# USB.net
KiCad netlist of a schematic drawn in Altium Designer
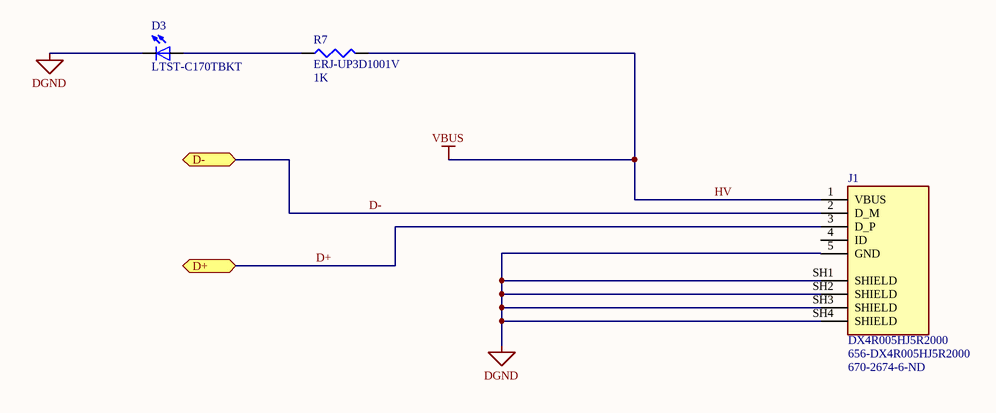
[diagram p0: USB.SchDoc]

(export (version "E")
  (design (tool "Eeschema 10.0.6"))
  (components
    (comp (ref "D3")
      (value "LTST-C170TBKT")
      (footprint "DIOC200X125X110")
      (description "Blue 470nm LED Indication - Discrete 3.3V 0805 _2012 Metric_")
      (fields (field (name "MF") "Lite-On Inc.") (field (name "DIGI-KEY_PART_NUMBER") "160-1579-1-ND"))
      (libsource (lib "Led") (part "LTST-C170TBKT"))
    )
    (comp (ref "J1")
      (value "DX4R005HJ5R2000")
      (footprint "DX4R005HJ5R2000:JAE_DX4R005HJ5R2000")
      (description "USB - micro B USB 2.0 Receptacle Connector 5 Position Surface Mount, Right Angle")
      (fields
        (field (name "MF") "JAE Electronics")
        (field (name "SUPPLIER PART NUMBER 1") "656-DX4R005HJ5R2000")
        (field (name "SUPPLIER PART NUMBER 2") "670-2674-6-ND")
      )
      (libsource (lib "DX4R005HJ5R2000") (part "DX4R005HJ5R2000"))
    )
    (comp (ref "R7")
      (value "ERJ-UP3D1001V")
      (footprint "J1-0603")
      (description "Resistor")
      (fields (field (name "ALTIUM_VALUE") "1K") (field (name "PUBLISHER") "Altium Limited"))
      (libsource (lib "Miscellaneous Devices") (part "Res3"))
    )
  )
  (nets
    (net (code "1") (name "/D+") (class "Default")
      (node (ref "J1") (pin "3") (pinfunction "D_P_3") (pintype "passive"))
    )
    (net (code "2") (name "/D-") (class "Default")
      (node (ref "J1") (pin "2") (pinfunction "D_M_2") (pintype "passive"))
    )
    (net (code "3") (name "DGND") (class "Default")
      (node (ref "D3") (pin "NEG") (pinfunction "NEG_NEG") (pintype "passive"))
      (node (ref "J1") (pin "5") (pinfunction "GND_5") (pintype "passive"))
      (node (ref "J1") (pin "SH1") (pinfunction "SHIELD_SH1") (pintype "passive"))
      (node (ref "J1") (pin "SH2") (pinfunction "SHIELD_SH2") (pintype "passive"))
      (node (ref "J1") (pin "SH3") (pinfunction "SHIELD_SH3") (pintype "passive"))
      (node (ref "J1") (pin "SH4") (pinfunction "SHIELD_SH4") (pintype "passive"))
    )
    (net (code "4") (name "Net-(D3-PadPOS)") (class "Default")
      (node (ref "D3") (pin "POS") (pinfunction "POS_POS") (pintype "passive"))
      (node (ref "R7") (pin "1") (pinfunction "1_1") (pintype "passive"))
    )
    (net (code "5") (name "VBUS") (class "Default")
      (node (ref "J1") (pin "1") (pinfunction "VBUS_1") (pintype "passive"))
      (node (ref "R7") (pin "2") (pinfunction "2_2") (pintype "passive"))
    )
    (net (code "6") (name "unconnected-(J1-ID-Pad4)") (class "Default")
      (node (ref "J1") (pin "4") (pinfunction "ID_4") (pintype "passive"))
    )
  )
)
